# MCUPower.net
KiCad netlist of a schematic drawn in Altium Designer
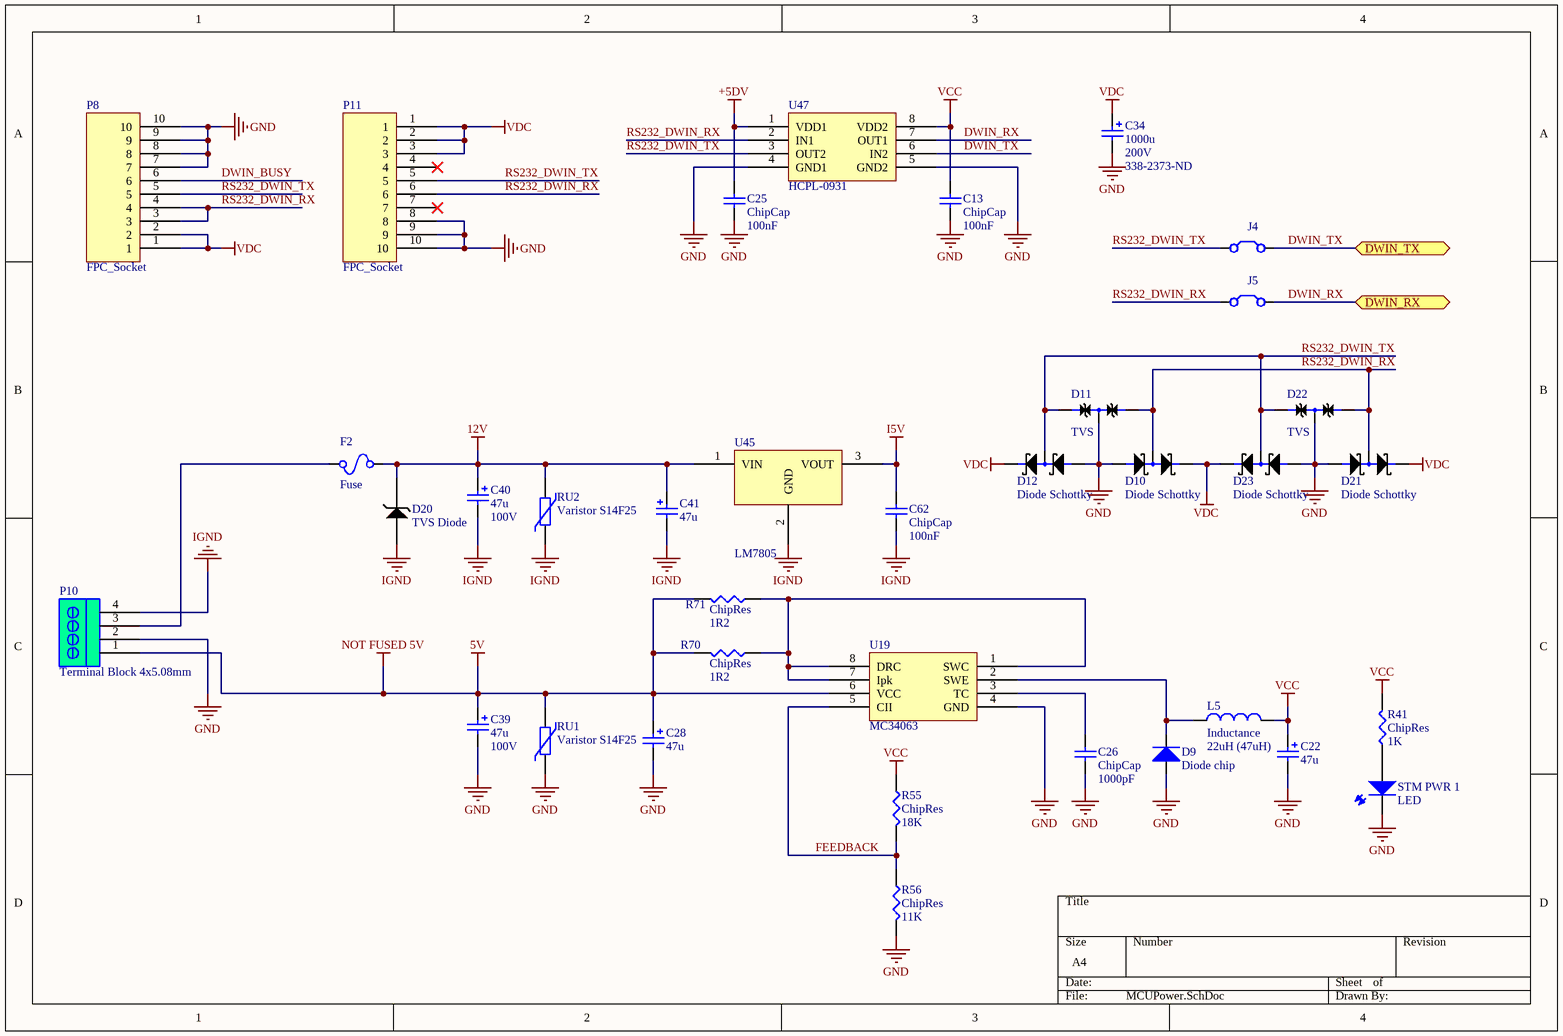
[diagram p0: MCUPower.SchDoc]

(export (version "E")
  (design (tool "Eeschema 10.0.6"))
  (components
    (comp (ref "C13")
      (value "ChipCap")
      (footprint "CAP0805")
      (description "Capacitor")
      (fields (field (name "ALTIUM_VALUE") "100nF") (field (name "PUBLISHER") "Altium Limited"))
      (libsource (lib "Common Devices") (part "ChipCap"))
    )
    (comp (ref "C22")
      (value "47u")
      (footprint "CAPC7343")
      (description "Polarized Capacitor (Radial)")
      (fields (field (name "Comment") "Cap Pol SMD"))
      (libsource (lib "Common Devices") (part "Cap Pol Chip"))
    )
    (comp (ref "C25")
      (value "ChipCap")
      (footprint "CAP0805")
      (description "Capacitor")
      (fields (field (name "ALTIUM_VALUE") "100nF") (field (name "PUBLISHER") "Altium Limited"))
      (libsource (lib "Common Devices") (part "ChipCap"))
    )
    (comp (ref "C26")
      (value "ChipCap")
      (footprint "CAP0805")
      (description "Capacitor")
      (fields (field (name "ALTIUM_VALUE") "1000pF") (field (name "PUBLISHER") "Altium Limited"))
      (libsource (lib "Common Devices") (part "ChipCap"))
    )
    (comp (ref "C28")
      (value "47u")
      (footprint "CAPC7343")
      (description "Polarized Capacitor (Radial)")
      (fields (field (name "Comment") "Cap Pol SMD"))
      (libsource (lib "Common Devices") (part "Cap Pol Chip"))
    )
    (comp (ref "C34")
      (value "1000u")
      (footprint "CAPPR7.5-16x25_1")
      (description "Polarized Capacitor (Radial)")
      (fields
        (field (name "VOLTAGE") "200V")
        (field (name "SUPPLIER PART NUMBER 1") "338-2373-ND")
        (field (name "Comment") "Cap Pol 200/100")
      )
      (libsource (lib "Common Devices") (part "Cap Pol 200/100"))
    )
    (comp (ref "C39")
      (value "47u")
      (footprint "CAPPR5-10x17_1")
      (description "Polarized Capacitor (Radial)")
      (fields (field (name "VOLTAGE") "100V") (field (name "Comment") "Cap Pol 100/47"))
      (libsource (lib "Common Devices") (part "Cap Pol 100/47"))
    )
    (comp (ref "C40")
      (value "47u")
      (footprint "CAPPR5-10x17_1")
      (description "Polarized Capacitor (Radial)")
      (fields (field (name "VOLTAGE") "100V") (field (name "Comment") "Cap Pol 100/47"))
      (libsource (lib "Common Devices") (part "Cap Pol 100/47"))
    )
    (comp (ref "C41")
      (value "47u")
      (footprint "CAPC7343")
      (description "Polarized Capacitor (Radial)")
      (fields (field (name "Comment") "Cap Pol SMD"))
      (libsource (lib "Common Devices") (part "Cap Pol Chip"))
    )
    (comp (ref "C62")
      (value "ChipCap")
      (footprint "CAP0805")
      (description "Capacitor")
      (fields (field (name "ALTIUM_VALUE") "100nF") (field (name "PUBLISHER") "Altium Limited"))
      (libsource (lib "Common Devices") (part "ChipCap"))
    )
    (comp (ref "D9")
      (value "Diode chip")
      (footprint "SMB1")
      (fields (field (name "VOLTAGE") "1000V"))
      (libsource (lib "Common Devices") (part "Diode chip"))
    )
    (comp (ref "D10")
      (value "Diode Schottky")
      (footprint "SOT23")
      (description "2-Diode Schottky")
      (libsource (lib "Protection") (part "Schottky Diode"))
    )
    (comp (ref "D11")
      (value "TVS")
      (footprint "SOT23")
      (description "Dual bidirectional voltage supresor")
      (libsource (lib "Protection") (part "TVS Diode"))
    )
    (comp (ref "D12")
      (value "Diode Schottky")
      (footprint "SOT23")
      (description "2-Diode Schottky")
      (libsource (lib "") (part "Schottky Diode_1"))
    )
    (comp (ref "D20")
      (value "TVS Diode")
      (footprint "DO-214AS")
      (libsource (lib "Protection") (part "TVS Diode SMA"))
    )
    (comp (ref "D21")
      (value "Diode Schottky")
      (footprint "SOT23")
      (description "2-Diode Schottky")
      (libsource (lib "Protection") (part "Schottky Diode"))
    )
    (comp (ref "D22")
      (value "TVS")
      (footprint "SOT23")
      (description "Dual bidirectional voltage supresor")
      (libsource (lib "Protection") (part "TVS Diode"))
    )
    (comp (ref "D23")
      (value "Diode Schottky")
      (footprint "SOT23")
      (description "2-Diode Schottky")
      (libsource (lib "") (part "Schottky Diode_1"))
    )
    (comp (ref "F2")
      (value "Fuse")
      (footprint "PTC1812")
      (description "Fuse PTC 1812 Thermoresistor")
      (libsource (lib "Protection") (part "Fuse PTC1812"))
    )
    (comp (ref "J4") (value "Jumper") (footprint "J0805") (libsource (lib "Common Devices") (part "Jumper")))
    (comp (ref "J5") (value "Jumper") (footprint "J0805") (libsource (lib "Common Devices") (part "Jumper")))
    (comp (ref "L5")
      (value "Inductance")
      (footprint "IHPL-3232")
      (fields (field (name "ALTIUM_VALUE") "22uH (47uH)"))
      (libsource (lib "Common Devices") (part "ChipInductance"))
    )
    (comp (ref "P8")
      (value "FPC_Socket")
      (footprint "MOLEX Header 8 2mm Pitch")
      (libsource (lib "RibbonConnectors") (part "FPC_Socket"))
    )
    (comp (ref "P10")
      (value "Terminal Block 4x5.08mm")
      (footprint "Socket 4x5.08")
      (description "Terminal Block Socket Right Angle 4x5.08mm 2-Wall")
      (libsource (lib "IndustrialConnectors") (part "Socket_4x5.08_RA_2Wall"))
    )
    (comp (ref "P11")
      (value "FPC_Socket")
      (footprint "Molex FPC/FFC 10pin")
      (libsource (lib "") (part "FPC_Socket_1"))
    )
    (comp (ref "R41")
      (value "ChipRes")
      (footprint "RES0805")
      (description "Chip resistor")
      (fields (field (name "ALTIUM_VALUE") "1K"))
      (libsource (lib "Common Devices") (part "ChipRes"))
    )
    (comp (ref "R55")
      (value "ChipRes")
      (footprint "RES0805")
      (description "Chip resistor")
      (fields (field (name "ALTIUM_VALUE") "18K"))
      (libsource (lib "Common Devices") (part "ChipRes"))
    )
    (comp (ref "R56")
      (value "ChipRes")
      (footprint "RES0805")
      (description "Chip resistor")
      (fields (field (name "ALTIUM_VALUE") "11K"))
      (libsource (lib "Common Devices") (part "ChipRes"))
    )
    (comp (ref "R70")
      (value "ChipRes")
      (footprint "RES0805")
      (description "Chip resistor")
      (fields (field (name "ALTIUM_VALUE") "1R2"))
      (libsource (lib "Common Devices") (part "ChipRes"))
    )
    (comp (ref "R71")
      (value "ChipRes")
      (footprint "RES0805")
      (description "Chip resistor")
      (fields (field (name "ALTIUM_VALUE") "1R2"))
      (libsource (lib "Common Devices") (part "ChipRes"))
    )
    (comp (ref "RU1")
      (value "Varistor S14F25")
      (footprint "S14K25")
      (description "varistor")
      (libsource (lib "Protection") (part "Varistor S14K25"))
    )
    (comp (ref "RU2")
      (value "Varistor S14F25")
      (footprint "S14K25")
      (description "varistor")
      (libsource (lib "Protection") (part "Varistor S14K25"))
    )
    (comp (ref "STM PWR 1") (value "LED") (footprint "PLCC-2") (libsource (lib "LEDs") (part "LED0603")))
    (comp (ref "U19")
      (value "MC34063")
      (footprint "SOP8")
      (description "DC/DC converter control circuit")
      (libsource (lib "ST ARM32") (part "MC34063"))
    )
    (comp (ref "U45")
      (value "LM7805")
      (footprint "TO-220")
      (description "Linear voltage regulator 1A")
      (libsource (lib "Fairchild") (part "LM7805"))
    )
    (comp (ref "U47")
      (value "HCPL-0931")
      (footprint "SOIC8")
      (description "2-bit bi-direction optoisolated buffer")
      (libsource (lib "AVAGO bi-direction optoisolated buffer") (part "HCPL-0931-000E"))
    )
  )
  (nets
    (net (code "1") (name "+5DV") (class "Default")
      (node (ref "C25") (pin "2") (pinfunction "2_2") (pintype "passive"))
      (node (ref "U47") (pin "1") (pinfunction "VDD1_1") (pintype "passive"))
    )
    (net (code "2") (name "/DWIN_BUSY") (class "Default")
      (node (ref "P8") (pin "6") (pinfunction "6_6") (pintype "passive"))
    )
    (net (code "3") (name "/DWIN_RX") (class "Default")
      (node (ref "J5") (pin "1") (pinfunction "1_1") (pintype "passive"))
      (node (ref "U47") (pin "7") (pinfunction "OUT1_7") (pintype "passive"))
    )
    (net (code "4") (name "/DWIN_TX") (class "Default")
      (node (ref "J4") (pin "1") (pinfunction "1_1") (pintype "passive"))
      (node (ref "U47") (pin "6") (pinfunction "IN2_6") (pintype "passive"))
    )
    (net (code "5") (name "/FEEDBACK") (class "Default")
      (node (ref "R55") (pin "2") (pintype "passive"))
      (node (ref "R56") (pin "1") (pintype "passive"))
      (node (ref "U19") (pin "5") (pinfunction "CII_5") (pintype "passive"))
    )
    (net (code "6") (name "/RS232_DWIN_RX") (class "Default")
      (node (ref "D10") (pin "3") (pinfunction "3_3") (pintype "passive"))
      (node (ref "D11") (pin "2") (pinfunction "2_2") (pintype "passive"))
      (node (ref "D21") (pin "3") (pinfunction "3_3") (pintype "passive"))
      (node (ref "D22") (pin "2") (pinfunction "2_2") (pintype "passive"))
      (node (ref "J5") (pin "0") (pinfunction "0_0") (pintype "passive"))
      (node (ref "P11") (pin "6") (pinfunction "6_6") (pintype "passive"))
      (node (ref "P8") (pin "3") (pinfunction "3_3") (pintype "passive"))
      (node (ref "P8") (pin "4") (pinfunction "4_4") (pintype "passive"))
      (node (ref "U47") (pin "2") (pinfunction "IN1_2") (pintype "passive"))
    )
    (net (code "7") (name "/RS232_DWIN_TX") (class "Default")
      (node (ref "D11") (pin "1") (pinfunction "1_1") (pintype "passive"))
      (node (ref "D12") (pin "3") (pinfunction "3_3") (pintype "passive"))
      (node (ref "D22") (pin "1") (pinfunction "1_1") (pintype "passive"))
      (node (ref "D23") (pin "3") (pinfunction "3_3") (pintype "passive"))
      (node (ref "J4") (pin "0") (pinfunction "0_0") (pintype "passive"))
      (node (ref "P11") (pin "5") (pinfunction "5_5") (pintype "passive"))
      (node (ref "P8") (pin "5") (pinfunction "5_5") (pintype "passive"))
      (node (ref "U47") (pin "3") (pinfunction "OUT2_3") (pintype "passive"))
    )
    (net (code "8") (name "5V") (class "Default")
      (node (ref "C28") (pin "1") (pinfunction "1_1") (pintype "passive"))
      (node (ref "C39") (pin "1") (pinfunction "1_1") (pintype "passive"))
      (node (ref "P10") (pin "1") (pintype "passive"))
      (node (ref "R70") (pin "2") (pintype "passive"))
      (node (ref "R71") (pin "2") (pintype "passive"))
      (node (ref "RU1") (pin "2") (pinfunction "2_2") (pintype "passive"))
      (node (ref "U19") (pin "6") (pinfunction "VCC_6") (pintype "passive"))
    )
    (net (code "9") (name "12V") (class "Default")
      (node (ref "C40") (pin "1") (pinfunction "1_1") (pintype "passive"))
      (node (ref "C41") (pin "1") (pinfunction "1_1") (pintype "passive"))
      (node (ref "D20") (pin "1") (pinfunction "1_1") (pintype "passive"))
      (node (ref "F2") (pin "1") (pinfunction "1_1") (pintype "passive"))
      (node (ref "RU2") (pin "2") (pinfunction "2_2") (pintype "passive"))
      (node (ref "U45") (pin "1") (pinfunction "VIN_1") (pintype "passive"))
    )
    (net (code "10") (name "GND") (class "Default")
      (node (ref "C13") (pin "1") (pinfunction "1_1") (pintype "passive"))
      (node (ref "C22") (pin "2") (pinfunction "2_2") (pintype "passive"))
      (node (ref "C25") (pin "1") (pinfunction "1_1") (pintype "passive"))
      (node (ref "C26") (pin "1") (pinfunction "1_1") (pintype "passive"))
      (node (ref "C28") (pin "2") (pinfunction "2_2") (pintype "passive"))
      (node (ref "C34") (pin "2") (pinfunction "2_2") (pintype "passive"))
      (node (ref "C39") (pin "2") (pinfunction "2_2") (pintype "passive"))
      (node (ref "D10") (pin "1") (pinfunction "1_1") (pintype "passive"))
      (node (ref "D11") (pin "3") (pinfunction "3_3") (pintype "passive"))
      (node (ref "D12") (pin "1") (pinfunction "1_1") (pintype "passive"))
      (node (ref "D21") (pin "1") (pinfunction "1_1") (pintype "passive"))
      (node (ref "D22") (pin "3") (pinfunction "3_3") (pintype "passive"))
      (node (ref "D23") (pin "1") (pinfunction "1_1") (pintype "passive"))
      (node (ref "D9") (pin "1") (pinfunction "A_1") (pintype "passive"))
      (node (ref "P10") (pin "2") (pintype "passive"))
      (node (ref "P11") (pin "10") (pinfunction "10_10") (pintype "passive"))
      (node (ref "P11") (pin "8") (pinfunction "8_8") (pintype "passive"))
      (node (ref "P11") (pin "9") (pinfunction "9_9") (pintype "passive"))
      (node (ref "P8") (pin "10") (pinfunction "10_10") (pintype "passive"))
      (node (ref "P8") (pin "7") (pinfunction "7_7") (pintype "passive"))
      (node (ref "P8") (pin "8") (pinfunction "8_8") (pintype "passive"))
      (node (ref "P8") (pin "9") (pinfunction "9_9") (pintype "passive"))
      (node (ref "R56") (pin "2") (pintype "passive"))
      (node (ref "RU1") (pin "1") (pinfunction "1_1") (pintype "passive"))
      (node (ref "STM PWR 1") (pin "1") (pinfunction "1_1") (pintype "passive"))
      (node (ref "U19") (pin "4") (pinfunction "GND_4") (pintype "passive"))
      (node (ref "U47") (pin "4") (pinfunction "GND1_4") (pintype "passive"))
      (node (ref "U47") (pin "5") (pinfunction "GND2_5") (pintype "passive"))
    )
    (net (code "11") (name "I5V") (class "Default")
      (node (ref "C62") (pin "2") (pinfunction "2_2") (pintype "passive"))
      (node (ref "U45") (pin "3") (pinfunction "VOUT_3") (pintype "passive"))
    )
    (net (code "12") (name "IGND") (class "Default")
      (node (ref "C40") (pin "2") (pinfunction "2_2") (pintype "passive"))
      (node (ref "C41") (pin "2") (pinfunction "2_2") (pintype "passive"))
      (node (ref "C62") (pin "1") (pinfunction "1_1") (pintype "passive"))
      (node (ref "D20") (pin "2") (pinfunction "2_2") (pintype "passive"))
      (node (ref "P10") (pin "4") (pintype "passive"))
      (node (ref "RU2") (pin "1") (pinfunction "1_1") (pintype "passive"))
      (node (ref "U45") (pin "2") (pinfunction "GND_2") (pintype "passive"))
    )
    (net (code "13") (name "Net-(D9-K)") (class "Default")
      (node (ref "D9") (pin "2") (pinfunction "K_2") (pintype "passive"))
      (node (ref "L5") (pin "2") (pintype "passive"))
      (node (ref "U19") (pin "2") (pinfunction "SWE_2") (pintype "passive"))
    )
    (net (code "14") (name "Net-(F2-Pad2)") (class "Default")
      (node (ref "F2") (pin "2") (pinfunction "2_2") (pintype "passive"))
      (node (ref "P10") (pin "3") (pintype "passive"))
    )
    (net (code "15") (name "Net-(R41-Pad1)") (class "Default")
      (node (ref "R41") (pin "1") (pintype "passive"))
      (node (ref "STM PWR 1") (pin "2") (pinfunction "2_2") (pintype "passive"))
    )
    (net (code "16") (name "Net-(U19-DRC)") (class "Default")
      (node (ref "R70") (pin "1") (pintype "passive"))
      (node (ref "R71") (pin "1") (pintype "passive"))
      (node (ref "U19") (pin "1") (pinfunction "SWC_1") (pintype "passive"))
      (node (ref "U19") (pin "7") (pinfunction "Ipk_7") (pintype "passive"))
      (node (ref "U19") (pin "8") (pinfunction "DRC_8") (pintype "passive"))
    )
    (net (code "17") (name "Net-(U19-TC)") (class "Default")
      (node (ref "C26") (pin "2") (pinfunction "2_2") (pintype "passive"))
      (node (ref "U19") (pin "3") (pinfunction "TC_3") (pintype "passive"))
    )
    (net (code "18") (name "VCC") (class "Default")
      (node (ref "C13") (pin "2") (pinfunction "2_2") (pintype "passive"))
      (node (ref "C22") (pin "1") (pinfunction "1_1") (pintype "passive"))
      (node (ref "L5") (pin "1") (pintype "passive"))
      (node (ref "R41") (pin "2") (pintype "passive"))
      (node (ref "R55") (pin "1") (pintype "passive"))
      (node (ref "U47") (pin "8") (pinfunction "VDD2_8") (pintype "passive"))
    )
    (net (code "19") (name "VDC") (class "Default")
      (node (ref "C34") (pin "1") (pinfunction "1_1") (pintype "passive"))
      (node (ref "D10") (pin "2") (pinfunction "2_2") (pintype "passive"))
      (node (ref "D12") (pin "2") (pinfunction "2_2") (pintype "passive"))
      (node (ref "D21") (pin "2") (pinfunction "2_2") (pintype "passive"))
      (node (ref "D23") (pin "2") (pinfunction "2_2") (pintype "passive"))
      (node (ref "P11") (pin "1") (pinfunction "1_1") (pintype "passive"))
      (node (ref "P11") (pin "2") (pinfunction "2_2") (pintype "passive"))
      (node (ref "P11") (pin "3") (pinfunction "3_3") (pintype "passive"))
      (node (ref "P8") (pin "1") (pinfunction "1_1") (pintype "passive"))
      (node (ref "P8") (pin "2") (pinfunction "2_2") (pintype "passive"))
    )
    (net (code "20") (name "unconnected-(P11-Pad4)") (class "Default")
      (node (ref "P11") (pin "4") (pinfunction "4_4") (pintype "passive+no_connect"))
    )
    (net (code "21") (name "unconnected-(P11-Pad7)") (class "Default")
      (node (ref "P11") (pin "7") (pinfunction "7_7") (pintype "passive+no_connect"))
    )
  )
)
